# Sheet.net
KiCad netlist of a schematic drawn in Altium Designer
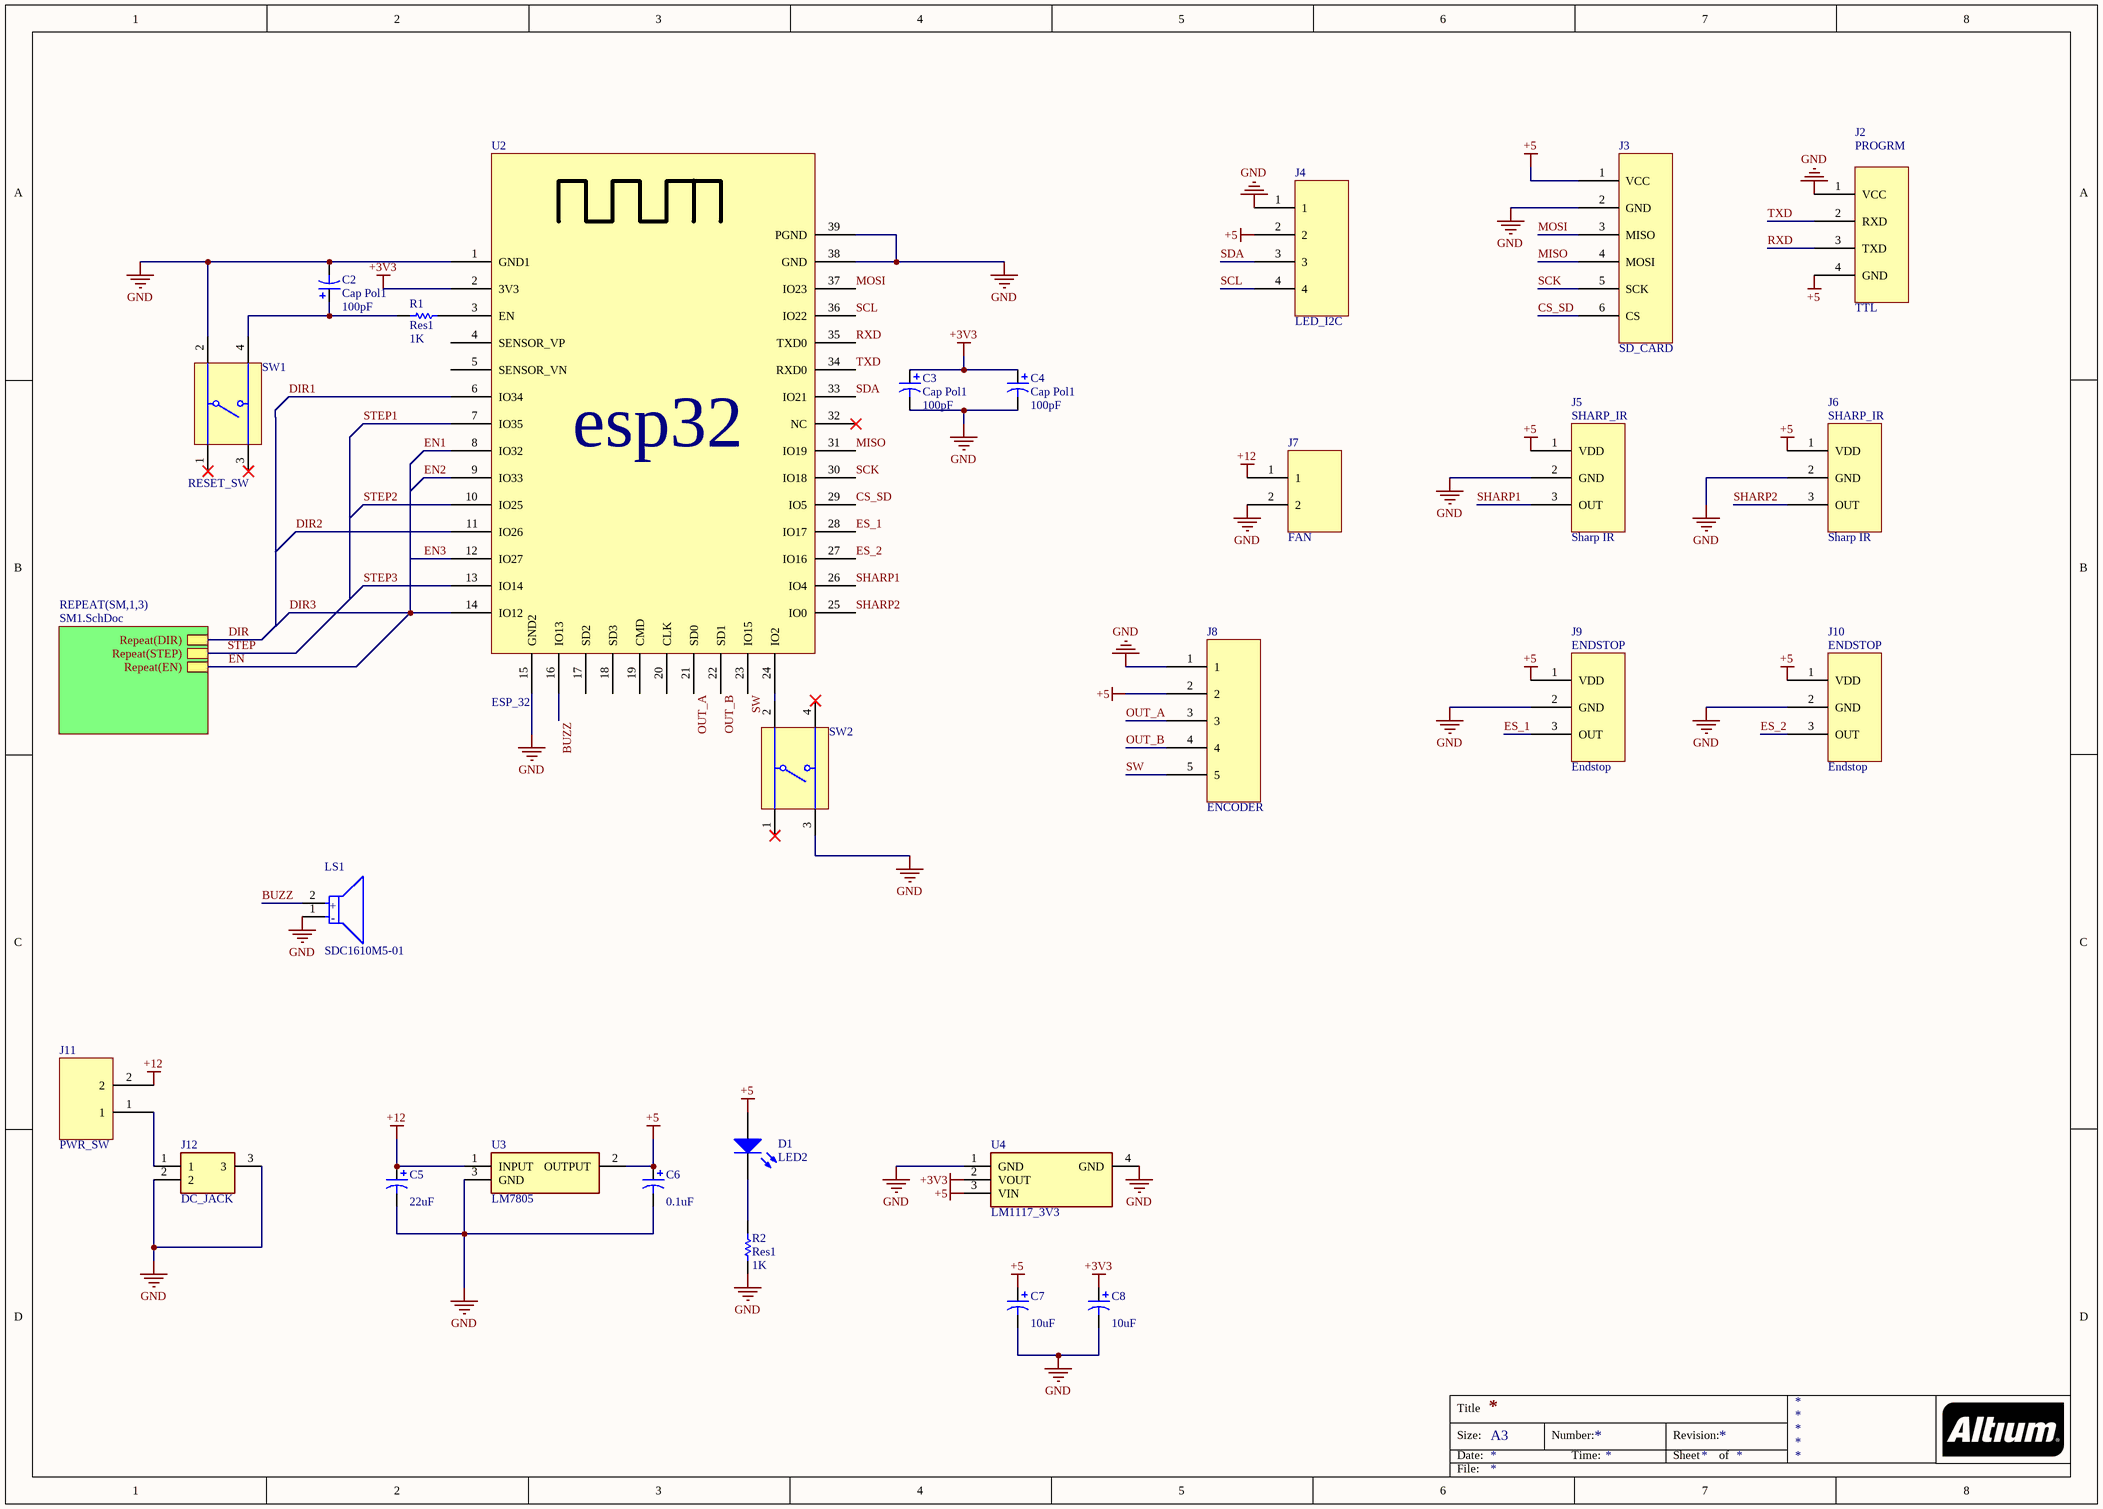
[diagram p0: Sheet.SchDoc]

(export (version "E")
  (design (tool "Eeschema 10.0.6"))
  (components
    (comp (ref "C2")
      (value "Cap Pol1")
      (footprint "6-0805_N")
      (description "Polarized Capacitor (Radial)")
      (fields (field (name "ALTIUM_VALUE") "100pF") (field (name "PUBLISHER") "Altium Limited"))
      (libsource (lib "Miscellaneous Devices") (part "Cap Pol1"))
    )
    (comp (ref "C3")
      (value "Cap Pol1")
      (footprint "6-0805_N")
      (description "Polarized Capacitor (Radial)")
      (fields (field (name "ALTIUM_VALUE") "100pF") (field (name "PUBLISHER") "Altium Limited"))
      (libsource (lib "Miscellaneous Devices") (part "Cap Pol1"))
    )
    (comp (ref "C4")
      (value "Cap Pol1")
      (footprint "6-0805_N")
      (description "Polarized Capacitor (Radial)")
      (fields (field (name "ALTIUM_VALUE") "100pF") (field (name "PUBLISHER") "Altium Limited"))
      (libsource (lib "Miscellaneous Devices") (part "Cap Pol1"))
    )
    (comp (ref "C5")
      (value "22uF")
      (footprint "6-0805_N")
      (description "Polarized Capacitor (Radial)")
      (fields (field (name "Comment") "Cap Pol1") (field (name "PUBLISHER") "Altium Limited"))
      (libsource (lib "Miscellaneous Devices") (part "Cap Pol1"))
    )
    (comp (ref "C6")
      (value "0.1uF")
      (footprint "6-0805_N")
      (description "Polarized Capacitor (Radial)")
      (fields (field (name "Comment") "Cap Pol1") (field (name "PUBLISHER") "Altium Limited"))
      (libsource (lib "Miscellaneous Devices") (part "Cap Pol1"))
    )
    (comp (ref "C7")
      (value "10uF")
      (footprint "6-0805_N")
      (description "Polarized Capacitor (Radial)")
      (fields (field (name "Comment") "Cap Pol1") (field (name "PUBLISHER") "Altium Limited"))
      (libsource (lib "Miscellaneous Devices") (part "Cap Pol1"))
    )
    (comp (ref "C8")
      (value "10uF")
      (footprint "6-0805_N")
      (description "Polarized Capacitor (Radial)")
      (fields (field (name "Comment") "Cap Pol1") (field (name "PUBLISHER") "Altium Limited"))
      (libsource (lib "Miscellaneous Devices") (part "Cap Pol1"))
    )
    (comp (ref "D1")
      (value "LED2")
      (footprint "3.2X1.6X1.1")
      (description "Typical RED, GREEN, YELLOW, AMBER GaAs LED")
      (fields (field (name "PUBLISHER") "Altium Limited"))
      (libsource (lib "Miscellaneous Devices") (part "LED2"))
    )
    (comp (ref "J2") (value "TTL") (footprint "TTL") (libsource (lib "Schlib") (part "TTL")))
    (comp (ref "J3") (value "SD_CARD") (footprint "SD_CARD") (libsource (lib "Schlib") (part "SD_CARD")))
    (comp (ref "J4") (value "LED_I2C") (footprint "JST_4P") (libsource (lib "Schlib") (part "JST_4P")))
    (comp (ref "J5") (value "Sharp IR") (footprint "SHARP_IR") (libsource (lib "Schlib") (part "SHARP_IR")))
    (comp (ref "J6") (value "Sharp IR") (footprint "SHARP_IR") (libsource (lib "Schlib") (part "SHARP_IR")))
    (comp (ref "J7") (value "FAN") (footprint "JST_2P") (libsource (lib "Schlib") (part "JST_2P")))
    (comp (ref "J8") (value "ENCODER") (footprint "JST_5P") (libsource (lib "Schlib") (part "JST_5P")))
    (comp (ref "J9") (value "Endstop") (footprint "ENDSTOP") (libsource (lib "Schlib") (part "ENDSTOP")))
    (comp (ref "J10") (value "Endstop") (footprint "ENDSTOP") (libsource (lib "Schlib") (part "ENDSTOP")))
    (comp (ref "J11") (value "PWR_SW") (footprint "JST_2P") (libsource (lib "") (part "JST_2P_1")))
    (comp (ref "J12") (value "DC_JACK") (footprint "DC_JACK") (libsource (lib "Schlib") (part "DC_JACK")))
    (comp (ref "LS1")
      (value "SDC1610M5-01")
      (footprint "FP-SDC1610M5-01-MFG")
      (description "AUDIO MAGNETIC INDICATOR 4-8V TH")
      (libsource (lib "Altium Content Vault") (part "f7ec632b6fea80cbef86dc3340f200c"))
    )
    (comp (ref "R1")
      (value "Res1")
      (footprint "6-0805_N")
      (description "Resistor")
      (fields (field (name "ALTIUM_VALUE") "1K") (field (name "PUBLISHER") "Altium Limited"))
      (libsource (lib "Miscellaneous Devices") (part "Res1"))
    )
    (comp (ref "R2")
      (value "Res1")
      (footprint "6-0805_N")
      (description "Resistor")
      (fields (field (name "ALTIUM_VALUE") "1K") (field (name "PUBLISHER") "Altium Limited"))
      (libsource (lib "Miscellaneous Devices") (part "Res1"))
    )
    (comp (ref "SW1")
      (value "RESET_SW")
      (footprint "TECO-1825910-6_V")
      (description "Tact Switch, SPST-NO, 0.05 A, -35 to 85 degC, 4-Pin THD, RoHS, Bulk")
      (fields (field (name "PART NO") "1825910-6") (field (name "MANUFACTURER") "TE Connectivity"))
      (libsource (lib "Altium Content Vault") (part "SW-SPST-4_A"))
    )
    (comp (ref "SW2")
      (value "1825910-6")
      (footprint "TECO-1825910-6_V")
      (description "Tact Switch, SPST-NO, 0.05 A, -35 to 85 degC, 4-Pin THD, RoHS, Bulk")
      (fields (field (name "MANUFACTURER") "TE Connectivity"))
      (libsource (lib "Altium Content Vault") (part "SW-SPST-4_A"))
    )
    (comp (ref "U2")
      (value "ESP_32")
      (footprint "ESP_SoC_Module")
      (libsource (lib "Schlib") (part "ESP_SoC_Module"))
    )
    (comp (ref "U3") (value "LM7805") (footprint "LM7805") (libsource (lib "Schlib") (part "LM7805")))
    (comp (ref "U4")
      (value "LM1117_3V3")
      (footprint "LM1117_3V3")
      (libsource (lib "Schlib") (part "LM1117_3V3"))
    )
  )
  (nets
    (net (code "1") (name "+3V3") (class "Default")
      (node (ref "C3") (pin "1") (pinfunction "1_1") (pintype "passive"))
      (node (ref "C4") (pin "1") (pinfunction "1_1") (pintype "passive"))
      (node (ref "C8") (pin "1") (pinfunction "1_1") (pintype "passive"))
      (node (ref "U2") (pin "2") (pinfunction "3V3_2") (pintype "passive"))
      (node (ref "U4") (pin "2") (pinfunction "VOUT_2") (pintype "passive"))
    )
    (net (code "2") (name "+5") (class "Default")
      (node (ref "C6") (pin "1") (pinfunction "1_1") (pintype "passive"))
      (node (ref "C7") (pin "1") (pinfunction "1_1") (pintype "passive"))
      (node (ref "D1") (pin "1") (pinfunction "A_1") (pintype "passive"))
      (node (ref "J10") (pin "1") (pinfunction "VDD_1") (pintype "passive"))
      (node (ref "J2") (pin "4") (pinfunction "GND_4") (pintype "passive"))
      (node (ref "J3") (pin "1") (pinfunction "VCC_1") (pintype "passive"))
      (node (ref "J4") (pin "2") (pinfunction "2_2") (pintype "passive"))
      (node (ref "J5") (pin "1") (pinfunction "VDD_1") (pintype "passive"))
      (node (ref "J6") (pin "1") (pinfunction "VDD_1") (pintype "passive"))
      (node (ref "J8") (pin "2") (pinfunction "2_2") (pintype "passive"))
      (node (ref "J9") (pin "1") (pinfunction "VDD_1") (pintype "passive"))
      (node (ref "U3") (pin "2") (pinfunction "OUTPUT_2") (pintype "passive"))
      (node (ref "U4") (pin "3") (pinfunction "VIN_3") (pintype "passive"))
    )
    (net (code "3") (name "+12") (class "Default")
      (node (ref "C5") (pin "1") (pinfunction "1_1") (pintype "passive"))
      (node (ref "J11") (pin "2") (pinfunction "2_2") (pintype "passive"))
      (node (ref "J7") (pin "1") (pinfunction "1_1") (pintype "passive"))
      (node (ref "U3") (pin "1") (pinfunction "INPUT_1") (pintype "passive"))
    )
    (net (code "4") (name "/BUZZ") (class "Default")
      (node (ref "LS1") (pin "2") (pinfunction "A_2") (pintype "passive"))
      (node (ref "U2") (pin "16") (pinfunction "IO13_16") (pintype "passive"))
    )
    (net (code "5") (name "/CS_SD") (class "Default")
      (node (ref "J3") (pin "6") (pinfunction "CS_6") (pintype "passive"))
      (node (ref "U2") (pin "29") (pinfunction "IO5_29") (pintype "passive"))
    )
    (net (code "7") (name "/DIR1") (class "Default")
      (node (ref "U2") (pin "6") (pinfunction "IO34_6") (pintype "passive"))
    )
    (net (code "8") (name "/DIR2") (class "Default")
      (node (ref "U2") (pin "11") (pinfunction "IO26_11") (pintype "passive"))
    )
    (net (code "9") (name "/DIR3") (class "Default")
      (node (ref "U2") (pin "14") (pinfunction "IO12_14") (pintype "passive"))
    )
    (net (code "11") (name "/EN1") (class "Default")
      (node (ref "U2") (pin "8") (pinfunction "IO32_8") (pintype "passive"))
    )
    (net (code "12") (name "/EN2") (class "Default")
      (node (ref "U2") (pin "9") (pinfunction "IO33_9") (pintype "passive"))
    )
    (net (code "13") (name "/EN3") (class "Default")
      (node (ref "U2") (pin "12") (pinfunction "IO27_12") (pintype "passive"))
    )
    (net (code "14") (name "/ES_1") (class "Default")
      (node (ref "J9") (pin "3") (pinfunction "OUT_3") (pintype "passive"))
      (node (ref "U2") (pin "28") (pinfunction "IO17_28") (pintype "passive"))
    )
    (net (code "15") (name "/ES_2") (class "Default")
      (node (ref "J10") (pin "3") (pinfunction "OUT_3") (pintype "passive"))
      (node (ref "U2") (pin "27") (pinfunction "IO16_27") (pintype "passive"))
    )
    (net (code "16") (name "/MISO") (class "Default")
      (node (ref "J3") (pin "4") (pinfunction "MOSI_4") (pintype "passive"))
      (node (ref "U2") (pin "31") (pinfunction "IO19_31") (pintype "passive"))
    )
    (net (code "17") (name "/MOSI") (class "Default")
      (node (ref "J3") (pin "3") (pinfunction "MISO_3") (pintype "passive"))
      (node (ref "U2") (pin "37") (pinfunction "IO23_37") (pintype "passive"))
    )
    (net (code "18") (name "/OUT_A") (class "Default")
      (node (ref "J8") (pin "3") (pinfunction "3_3") (pintype "passive"))
      (node (ref "U2") (pin "21") (pinfunction "SD0_21") (pintype "passive"))
    )
    (net (code "19") (name "/OUT_B") (class "Default")
      (node (ref "J8") (pin "4") (pinfunction "4_4") (pintype "passive"))
      (node (ref "U2") (pin "22") (pinfunction "SD1_22") (pintype "passive"))
    )
    (net (code "20") (name "/RXD") (class "Default")
      (node (ref "J2") (pin "3") (pinfunction "TXD_3") (pintype "passive"))
      (node (ref "U2") (pin "35") (pinfunction "TXD0_35") (pintype "passive"))
    )
    (net (code "21") (name "/SCK") (class "Default")
      (node (ref "J3") (pin "5") (pinfunction "SCK_5") (pintype "passive"))
      (node (ref "U2") (pin "30") (pinfunction "IO18_30") (pintype "passive"))
    )
    (net (code "22") (name "/SCL") (class "Default")
      (node (ref "J4") (pin "4") (pinfunction "4_4") (pintype "passive"))
      (node (ref "U2") (pin "36") (pinfunction "IO22_36") (pintype "passive"))
    )
    (net (code "23") (name "/SDA") (class "Default")
      (node (ref "J4") (pin "3") (pinfunction "3_3") (pintype "passive"))
      (node (ref "U2") (pin "33") (pinfunction "IO21_33") (pintype "passive"))
    )
    (net (code "24") (name "/SHARP1") (class "Default")
      (node (ref "J5") (pin "3") (pinfunction "OUT_3") (pintype "passive"))
      (node (ref "U2") (pin "26") (pinfunction "IO4_26") (pintype "passive"))
    )
    (net (code "25") (name "/SHARP2") (class "Default")
      (node (ref "J6") (pin "3") (pinfunction "OUT_3") (pintype "passive"))
      (node (ref "U2") (pin "25") (pinfunction "IO0_25") (pintype "passive"))
    )
    (net (code "27") (name "/STEP1") (class "Default")
      (node (ref "U2") (pin "7") (pinfunction "IO35_7") (pintype "passive"))
    )
    (net (code "28") (name "/STEP2") (class "Default")
      (node (ref "U2") (pin "10") (pinfunction "IO25_10") (pintype "passive"))
    )
    (net (code "29") (name "/STEP3") (class "Default")
      (node (ref "U2") (pin "13") (pinfunction "IO14_13") (pintype "passive"))
    )
    (net (code "30") (name "/SW") (class "Default")
      (node (ref "J8") (pin "5") (pinfunction "5_5") (pintype "passive"))
      (node (ref "U2") (pin "23") (pinfunction "IO15_23") (pintype "passive"))
    )
    (net (code "31") (name "/TXD") (class "Default")
      (node (ref "J2") (pin "2") (pinfunction "RXD_2") (pintype "passive"))
      (node (ref "U2") (pin "34") (pinfunction "RXD0_34") (pintype "passive"))
    )
    (net (code "32") (name "GND") (class "Default")
      (node (ref "C2") (pin "2") (pinfunction "2_2") (pintype "passive"))
      (node (ref "C3") (pin "2") (pinfunction "2_2") (pintype "passive"))
      (node (ref "C4") (pin "2") (pinfunction "2_2") (pintype "passive"))
      (node (ref "C5") (pin "2") (pinfunction "2_2") (pintype "passive"))
      (node (ref "C6") (pin "2") (pinfunction "2_2") (pintype "passive"))
      (node (ref "C7") (pin "2") (pinfunction "2_2") (pintype "passive"))
      (node (ref "C8") (pin "2") (pinfunction "2_2") (pintype "passive"))
      (node (ref "J10") (pin "2") (pinfunction "GND_2") (pintype "passive"))
      (node (ref "J12") (pin "2") (pinfunction "2_2") (pintype "passive"))
      (node (ref "J12") (pin "3") (pinfunction "3_3") (pintype "passive"))
      (node (ref "J2") (pin "1") (pinfunction "VCC_1") (pintype "passive"))
      (node (ref "J3") (pin "2") (pinfunction "GND_2") (pintype "passive"))
      (node (ref "J4") (pin "1") (pinfunction "1_1") (pintype "passive"))
      (node (ref "J5") (pin "2") (pinfunction "GND_2") (pintype "passive"))
      (node (ref "J6") (pin "2") (pinfunction "GND_2") (pintype "passive"))
      (node (ref "J7") (pin "2") (pinfunction "2_2") (pintype "passive"))
      (node (ref "J8") (pin "1") (pinfunction "1_1") (pintype "passive"))
      (node (ref "J9") (pin "2") (pinfunction "GND_2") (pintype "passive"))
      (node (ref "LS1") (pin "1") (pinfunction "C_1") (pintype "passive"))
      (node (ref "R2") (pin "1") (pinfunction "1_1") (pintype "passive"))
      (node (ref "SW1") (pin "2") (pinfunction "2_2") (pintype "passive"))
      (node (ref "SW2") (pin "3") (pinfunction "3_3") (pintype "passive"))
      (node (ref "U2") (pin "1") (pinfunction "GND1_1") (pintype "passive"))
      (node (ref "U2") (pin "15") (pinfunction "GND2_15") (pintype "passive"))
      (node (ref "U2") (pin "38") (pinfunction "GND_38") (pintype "passive"))
      (node (ref "U2") (pin "39") (pinfunction "PGND_39") (pintype "passive"))
      (node (ref "U3") (pin "3") (pinfunction "GND_3") (pintype "passive"))
      (node (ref "U4") (pin "1") (pinfunction "GND_1") (pintype "passive"))
      (node (ref "U4") (pin "4") (pinfunction "GND_4") (pintype "passive"))
    )
    (net (code "33") (name "Net-(C2-Pad1)") (class "Default")
      (node (ref "C2") (pin "1") (pinfunction "1_1") (pintype "passive"))
      (node (ref "R1") (pin "1") (pinfunction "1_1") (pintype "passive"))
      (node (ref "SW1") (pin "4") (pinfunction "4_4") (pintype "passive"))
    )
    (net (code "34") (name "Net-(D1-K)") (class "Default")
      (node (ref "D1") (pin "2") (pinfunction "K_2") (pintype "passive"))
      (node (ref "R2") (pin "2") (pinfunction "2_2") (pintype "passive"))
    )
    (net (code "35") (name "Net-(J11-Pad1)") (class "Default")
      (node (ref "J11") (pin "1") (pinfunction "1_1") (pintype "passive"))
      (node (ref "J12") (pin "1") (pinfunction "1_1") (pintype "passive"))
    )
    (net (code "36") (name "Net-(U2-EN)") (class "Default")
      (node (ref "R1") (pin "2") (pinfunction "2_2") (pintype "passive"))
      (node (ref "U2") (pin "3") (pinfunction "EN_3") (pintype "passive"))
    )
    (net (code "37") (name "Net-(U2-IO2)") (class "Default")
      (node (ref "SW2") (pin "2") (pinfunction "2_2") (pintype "passive"))
      (node (ref "U2") (pin "24") (pinfunction "IO2_24") (pintype "passive"))
    )
    (net (code "38") (name "unconnected-(SW1-Pad1)") (class "Default")
      (node (ref "SW1") (pin "1") (pinfunction "1_1") (pintype "passive+no_connect"))
    )
    (net (code "39") (name "unconnected-(SW1-Pad3)") (class "Default")
      (node (ref "SW1") (pin "3") (pinfunction "3_3") (pintype "passive+no_connect"))
    )
    (net (code "40") (name "unconnected-(SW2-Pad1)") (class "Default")
      (node (ref "SW2") (pin "1") (pinfunction "1_1") (pintype "passive+no_connect"))
    )
    (net (code "41") (name "unconnected-(SW2-Pad4)") (class "Default")
      (node (ref "SW2") (pin "4") (pinfunction "4_4") (pintype "passive+no_connect"))
    )
    (net (code "42") (name "unconnected-(U2-CLK-Pad20)") (class "Default")
      (node (ref "U2") (pin "20") (pinfunction "CLK_20") (pintype "passive"))
    )
    (net (code "43") (name "unconnected-(U2-CMD-Pad19)") (class "Default")
      (node (ref "U2") (pin "19") (pinfunction "CMD_19") (pintype "passive"))
    )
    (net (code "44") (name "unconnected-(U2-NC-Pad32)") (class "Default")
      (node (ref "U2") (pin "32") (pinfunction "NC_32") (pintype "passive+no_connect"))
    )
    (net (code "45") (name "unconnected-(U2-SD2-Pad17)") (class "Default")
      (node (ref "U2") (pin "17") (pinfunction "SD2_17") (pintype "passive"))
    )
    (net (code "46") (name "unconnected-(U2-SD3-Pad18)") (class "Default")
      (node (ref "U2") (pin "18") (pinfunction "SD3_18") (pintype "passive"))
    )
    (net (code "47") (name "unconnected-(U2-SENSOR_VN-Pad5)") (class "Default")
      (node (ref "U2") (pin "5") (pinfunction "SENSOR_VN_5") (pintype "passive"))
    )
    (net (code "48") (name "unconnected-(U2-SENSOR_VP-Pad4)") (class "Default")
      (node (ref "U2") (pin "4") (pinfunction "SENSOR_VP_4") (pintype "passive"))
    )
  )
)
